# Sheet1.net
KiCad netlist of a schematic drawn in Altium Designer
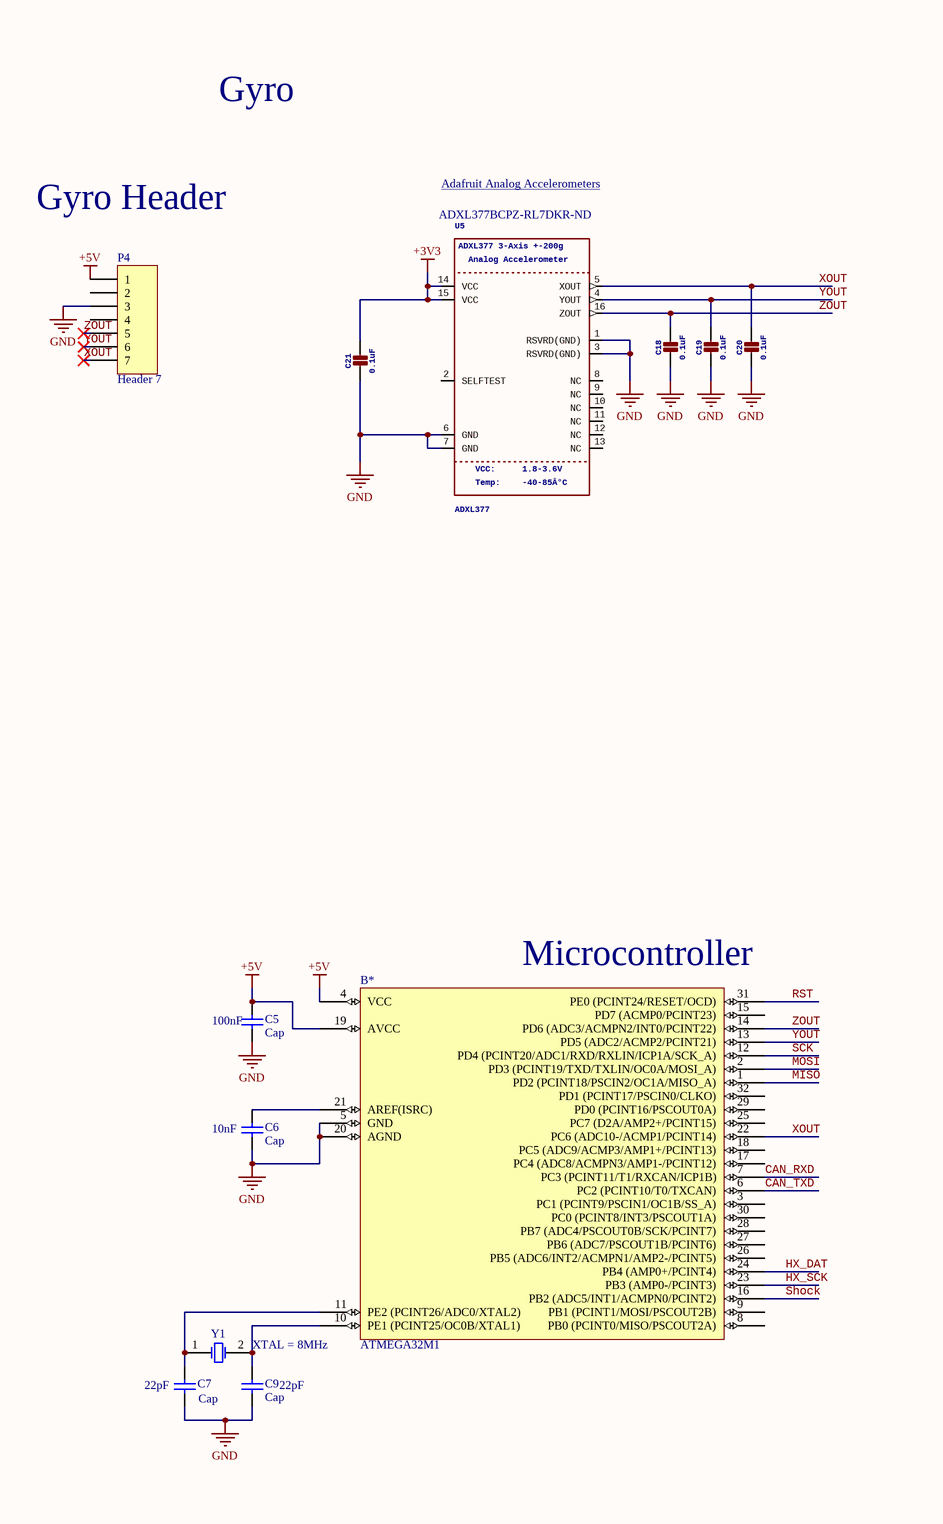
[diagram p0: Sheet1.SchDoc, left]
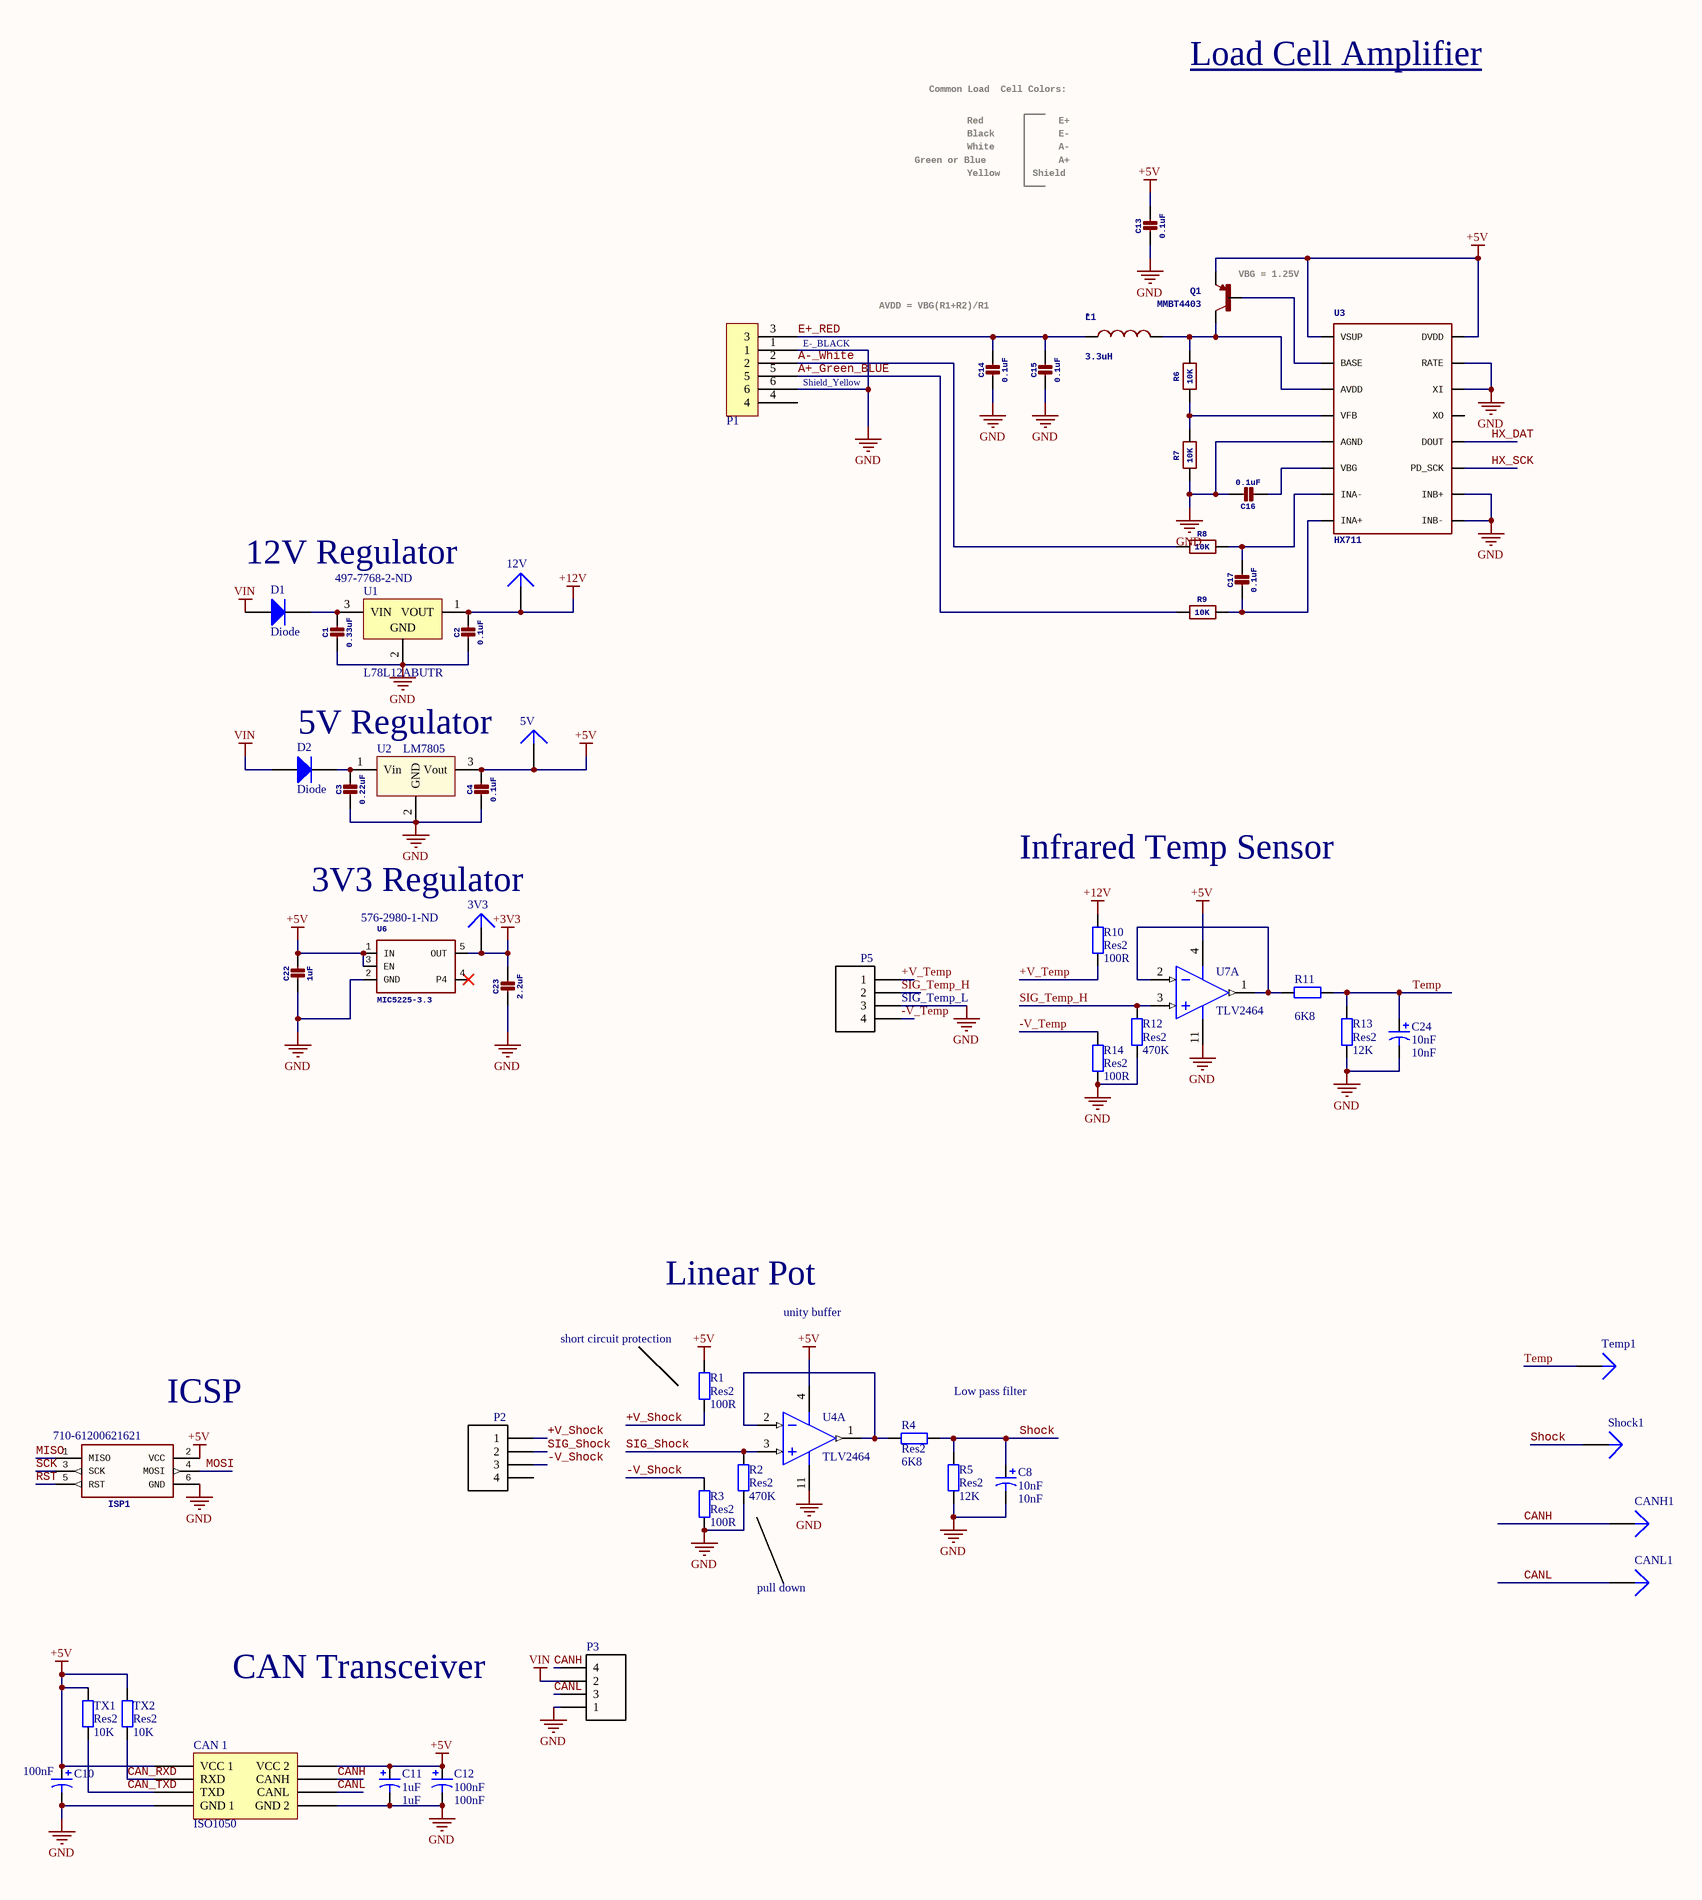
[diagram p1: Sheet1.SchDoc, right]

(export (version "E")
  (design (tool "Eeschema 10.0.6"))
  (components
    (comp (ref "3V3")
      (value "TP")
      (footprint "SMD_TP")
      (description "Test Point")
      (fields (field (name "PUBLISHER") "Altium Limited"))
      (libsource (lib "Miscellaneous Connectors") (part "Plug"))
    )
    (comp (ref "5V")
      (value "TP")
      (footprint "SMD_TP")
      (description "Test Point")
      (fields (field (name "PUBLISHER") "Altium Limited"))
      (libsource (lib "Miscellaneous Connectors") (part "Plug"))
    )
    (comp (ref "12V")
      (value "TP")
      (footprint "SMD_TP")
      (description "Test Point")
      (fields (field (name "PUBLISHER") "Altium Limited"))
      (libsource (lib "Miscellaneous Connectors") (part "Plug"))
    )
    (comp (ref "B*")
      (value "ATMEGA32M1")
      (footprint "QFP80P900X900X120-32N")
      (libsource (lib "Schlib1") (part "ATMEGA32M1"))
    )
    (comp (ref "C1")
      (value "0.33uF")
      (footprint "6-0805_M")
      (libsource (lib "Schlib1") (part "CAP_CERAMIC0805-NOOUTLINE"))
    )
    (comp (ref "C2")
      (value "0.1uF")
      (footprint "6-0805_M")
      (libsource (lib "Schlib1") (part "CAP_CERAMIC0805-NOOUTLINE"))
    )
    (comp (ref "C3")
      (value "0.22uF")
      (footprint "6-0805_M")
      (libsource (lib "Schlib1") (part "CAP_CERAMIC0805-NOOUTLINE"))
    )
    (comp (ref "C4")
      (value "0.1uF")
      (footprint "6-0805_M")
      (libsource (lib "Schlib1") (part "CAP_CERAMIC0805-NOOUTLINE"))
    )
    (comp (ref "C5")
      (value "Cap")
      (footprint "CAP-0805")
      (description "Capacitor")
      (fields (field (name "ALTIUM_VALUE") "100nF") (field (name "PUBLISHER") "Altium Limited"))
      (libsource (lib "Miscellaneous Devices") (part "Cap"))
    )
    (comp (ref "C6")
      (value "Cap")
      (footprint "CAP-0805")
      (description "Capacitor")
      (fields (field (name "ALTIUM_VALUE") "10nF") (field (name "PUBLISHER") "Altium Limited"))
      (libsource (lib "Miscellaneous Devices") (part "Cap"))
    )
    (comp (ref "C7")
      (value "Cap")
      (footprint "CAP-0805")
      (description "Capacitor")
      (fields (field (name "ALTIUM_VALUE") "22pF") (field (name "PUBLISHER") "Altium Limited"))
      (libsource (lib "Miscellaneous Devices") (part "Cap"))
    )
    (comp (ref "C8")
      (value "10nF")
      (footprint "6-0805_M")
      (description "Polarized Capacitor (Surface Mount)")
      (fields (field (name "ALTIUM_VALUE") "10nF") (field (name "PUBLISHER") "Altium Limited"))
      (libsource (lib "Miscellaneous Devices") (part "Cap Pol3"))
    )
    (comp (ref "C9")
      (value "Cap")
      (footprint "CAP-0805")
      (description "Capacitor")
      (fields (field (name "ALTIUM_VALUE") "22pF") (field (name "PUBLISHER") "Altium Limited"))
      (libsource (lib "Miscellaneous Devices") (part "Cap"))
    )
    (comp (ref "C10")
      (value "100nF")
      (footprint "6-0805_M")
      (description "Polarized Capacitor (Surface Mount)")
      (fields (field (name "PUBLISHER") "Altium Limited"))
      (libsource (lib "Miscellaneous Devices") (part "Cap Pol3"))
    )
    (comp (ref "C11")
      (value "1uF")
      (footprint "6-0805_M")
      (description "Polarized Capacitor (Surface Mount)")
      (fields (field (name "ALTIUM_VALUE") "1uF") (field (name "PUBLISHER") "Altium Limited"))
      (libsource (lib "") (part "Cap Pol3_1"))
    )
    (comp (ref "C12")
      (value "100nF")
      (footprint "6-0805_M")
      (description "Polarized Capacitor (Surface Mount)")
      (fields (field (name "ALTIUM_VALUE") "100nF") (field (name "PUBLISHER") "Altium Limited"))
      (libsource (lib "") (part "Cap Pol3_1"))
    )
    (comp (ref "C13")
      (value "0.1uF")
      (footprint "6-0805_M")
      (libsource (lib "Schlib1") (part "CAP_CERAMIC0805-NOOUTLINE"))
    )
    (comp (ref "C14")
      (value "0.1uF")
      (footprint "6-0805_M")
      (libsource (lib "Schlib1") (part "CAP_CERAMIC0805-NOOUTLINE"))
    )
    (comp (ref "C15")
      (value "0.1uF")
      (footprint "6-0805_M")
      (libsource (lib "Schlib1") (part "CAP_CERAMIC0805-NOOUTLINE"))
    )
    (comp (ref "C16")
      (value "0.1uF")
      (footprint "6-0805_M")
      (libsource (lib "") (part "CAP_CERAMIC0805-NOOUTLINE_1"))
    )
    (comp (ref "C17")
      (value "0.1uF")
      (footprint "6-0805_M")
      (libsource (lib "Schlib1") (part "CAP_CERAMIC0805-NOOUTLINE"))
    )
    (comp (ref "C18")
      (value "0.1uF")
      (footprint "0805_10MGAP")
      (libsource (lib "Schlib1") (part "CAP_CERAMIC0805_10MGAP"))
    )
    (comp (ref "C19")
      (value "0.1uF")
      (footprint "0805_10MGAP")
      (libsource (lib "Schlib1") (part "CAP_CERAMIC0805_10MGAP"))
    )
    (comp (ref "C20")
      (value "0.1uF")
      (footprint "0805_10MGAP")
      (libsource (lib "Schlib1") (part "CAP_CERAMIC0805_10MGAP"))
    )
    (comp (ref "C21")
      (value "0.1uF")
      (footprint "0805_10MGAP")
      (libsource (lib "Schlib1") (part "CAP_CERAMIC0805_10MGAP"))
    )
    (comp (ref "C22")
      (value "1uF")
      (footprint "6-0805_M")
      (libsource (lib "Schlib1") (part "CAP_CERAMIC0805-NOOUTLINE"))
    )
    (comp (ref "C23")
      (value "2.2uF")
      (footprint "6-0805_M")
      (libsource (lib "Schlib1") (part "CAP_CERAMIC0805-NOOUTLINE"))
    )
    (comp (ref "C24")
      (value "10nF")
      (footprint "6-0805_M")
      (description "Polarized Capacitor (Surface Mount)")
      (fields (field (name "ALTIUM_VALUE") "10nF") (field (name "PUBLISHER") "Altium Limited"))
      (libsource (lib "Miscellaneous Devices") (part "Cap Pol3"))
    )
    (comp (ref "CAN 1")
      (value "ISO1050")
      (footprint "PcbLib1:ISO1050")
      (description "ISO1050 Isolated Can Transceiver")
      (libsource (lib "Schlib1") (part "ISO1050"))
    )
    (comp (ref "CANH1")
      (value "TP")
      (footprint "SMD_TP")
      (description "Test Point")
      (fields (field (name "PUBLISHER") "Altium Limited"))
      (libsource (lib "Miscellaneous Connectors") (part "Plug"))
    )
    (comp (ref "CANL1")
      (value "TP")
      (footprint "SMD_TP")
      (description "Test Point")
      (fields (field (name "PUBLISHER") "Altium Limited"))
      (libsource (lib "Miscellaneous Connectors") (part "Plug"))
    )
    (comp (ref "D1")
      (value "Diode")
      (footprint "6-0805_M")
      (description "Default Diode")
      (fields (field (name "PUBLISHER") "Altium Limited"))
      (libsource (lib "Miscellaneous Devices") (part "Diode"))
    )
    (comp (ref "D2")
      (value "Diode")
      (footprint "6-0805_M")
      (description "Default Diode")
      (fields (field (name "PUBLISHER") "Altium Limited"))
      (libsource (lib "Miscellaneous Devices") (part "Diode"))
    )
    (comp (ref "ISP1")
      (value "AVRISP-BOX")
      (footprint "HDR2X3")
      (description "AVR ISP HEADERStandard 6 pin header for AVR programming")
      (fields
        (field (name "SUPPLIER PART NUMBER 1") "710-61200621621")
        (field (name "MANUFACTURER") "Wurth Electronics")
        (field (name "MANUFACTURER PART NUMBER") "61200621621")
      )
      (libsource (lib "Schlib1") (part "AVRISP-BOX"))
    )
    (comp (ref "L1")
      (value "3.3uH")
      (footprint "6-0805_M")
      (fields (field (name "NAME") "*"))
      (libsource (lib "SparkFun-Passives") (part "INDUCTOR0805-IND"))
    )
    (comp (ref "P1")
      (value "S06B-PASK-2")
      (footprint "JST_S06B-PASK-2")
      (description "JST (JAPAN SOLDERLESS TERMINALS) - S06B-PASK-2 - HEADER, PA, 6WAY, SIDE, 2MM")
      (libsource (lib "Schlib1") (part "JST-S06B-PASK-2"))
    )
    (comp (ref "P2")
      (value "S04B-PASK-2(LF)(SN)")
      (footprint "JST_S04B-PASK-2(LF)(SN)")
      (description "PA Series 4 Position 2.0mm Through Hole Wire to Board Single Row Shrouded Header")
      (fields (field (name "MP") "S04B-PASK-2_LF__SN_") (field (name "MF") "JST"))
      (libsource (lib "") (part "JST-S04B-PASK-2(LF)(SN)_1"))
    )
    (comp (ref "P3")
      (value "S04B-PASK-2(LF)(SN)")
      (footprint "JST_S04B-PASK-2(LF)(SN)")
      (description "PA Series 4 Position 2.0mm Through Hole Wire to Board Single Row Shrouded Header")
      (fields (field (name "MP") "S04B-PASK-2_LF__SN_") (field (name "MF") "JST"))
      (libsource (lib "Schlib1") (part "JST-S04B-PASK-2(LF)(SN)"))
    )
    (comp (ref "P4")
      (value "Header 7")
      (footprint "HDR1X7")
      (description "Header, 7-Pin")
      (fields (field (name "PUBLISHER") "Altium Limited"))
      (libsource (lib "Miscellaneous Connectors") (part "Header 7"))
    )
    (comp (ref "P5")
      (value "S04B-PASK-2(LF)(SN)")
      (footprint "JST_S04B-PASK-2(LF)(SN)")
      (description "PA Series 4 Position 2.0mm Through Hole Wire to Board Single Row Shrouded Header")
      (fields (field (name "MP") "S04B-PASK-2_LF__SN_") (field (name "MF") "JST"))
      (libsource (lib "") (part "JST-S04B-PASK-2(LF)(SN)_1"))
    )
    (comp (ref "Q1")
      (value "MMBT4403")
      (footprint "SOT23-3")
      (libsource (lib "SparkFun-DiscreteSemi") (part "TRANSISTOR_PNPMMBT4403"))
    )
    (comp (ref "R1")
      (value "Res2")
      (footprint "6-0805_M")
      (description "Resistor")
      (fields (field (name "ALTIUM_VALUE") "100R") (field (name "PUBLISHER") "Altium Limited"))
      (libsource (lib "Miscellaneous Devices") (part "Res2"))
    )
    (comp (ref "R2")
      (value "Res2")
      (footprint "6-0805_M")
      (description "Resistor")
      (fields (field (name "ALTIUM_VALUE") "470K") (field (name "PUBLISHER") "Altium Limited"))
      (libsource (lib "Miscellaneous Devices") (part "Res2"))
    )
    (comp (ref "R3")
      (value "Res2")
      (footprint "6-0805_M")
      (description "Resistor")
      (fields (field (name "ALTIUM_VALUE") "100R") (field (name "PUBLISHER") "Altium Limited"))
      (libsource (lib "Miscellaneous Devices") (part "Res2"))
    )
    (comp (ref "R4")
      (value "Res2")
      (footprint "6-0805_M")
      (description "Resistor")
      (fields (field (name "ALTIUM_VALUE") "6K8") (field (name "PUBLISHER") "Altium Limited"))
      (libsource (lib "") (part "Res2_1"))
    )
    (comp (ref "R5")
      (value "Res2")
      (footprint "6-0805_M")
      (description "Resistor")
      (fields (field (name "ALTIUM_VALUE") "12K") (field (name "PUBLISHER") "Altium Limited"))
      (libsource (lib "Miscellaneous Devices") (part "Res2"))
    )
    (comp (ref "R6")
      (value "10K")
      (footprint "6-0805_M")
      (libsource (lib "Schlib1") (part "RESISTOR0805_NOOUTLINE"))
    )
    (comp (ref "R7")
      (value "10K")
      (footprint "6-0805_M")
      (libsource (lib "Schlib1") (part "RESISTOR0805_NOOUTLINE"))
    )
    (comp (ref "R8")
      (value "10K")
      (footprint "6-0805_M")
      (libsource (lib "Schlib1") (part "RESISTOR0805_NOOUTLINE"))
    )
    (comp (ref "R9")
      (value "10K")
      (footprint "6-0805_M")
      (libsource (lib "Schlib1") (part "RESISTOR0805_NOOUTLINE"))
    )
    (comp (ref "R10")
      (value "Res2")
      (footprint "6-0805_M")
      (description "Resistor")
      (fields (field (name "ALTIUM_VALUE") "100R") (field (name "PUBLISHER") "Altium Limited"))
      (libsource (lib "Miscellaneous Devices") (part "Res2"))
    )
    (comp (ref "R11")
      (value "6K8")
      (footprint "6-0805_M")
      (description "Resistor")
      (fields (field (name "PUBLISHER") "Altium Limited"))
      (libsource (lib "") (part "Res2_1"))
    )
    (comp (ref "R12")
      (value "Res2")
      (footprint "6-0805_M")
      (description "Resistor")
      (fields (field (name "ALTIUM_VALUE") "470K") (field (name "PUBLISHER") "Altium Limited"))
      (libsource (lib "Miscellaneous Devices") (part "Res2"))
    )
    (comp (ref "R13")
      (value "Res2")
      (footprint "6-0805_M")
      (description "Resistor")
      (fields (field (name "ALTIUM_VALUE") "12K") (field (name "PUBLISHER") "Altium Limited"))
      (libsource (lib "Miscellaneous Devices") (part "Res2"))
    )
    (comp (ref "R14")
      (value "Res2")
      (footprint "6-0805_M")
      (description "Resistor")
      (fields (field (name "ALTIUM_VALUE") "100R") (field (name "PUBLISHER") "Altium Limited"))
      (libsource (lib "Miscellaneous Devices") (part "Res2"))
    )
    (comp (ref "Shock1")
      (value "TP")
      (footprint "SMD_TP")
      (description "Test Point")
      (fields (field (name "PUBLISHER") "Altium Limited"))
      (libsource (lib "Miscellaneous Connectors") (part "Plug"))
    )
    (comp (ref "Temp1")
      (value "TP")
      (footprint "SMD_TP")
      (description "Test Point")
      (fields (field (name "PUBLISHER") "Altium Limited"))
      (libsource (lib "Miscellaneous Connectors") (part "Plug"))
    )
    (comp (ref "TX1")
      (value "Res2")
      (footprint "6-0805_M")
      (description "Resistor")
      (fields (field (name "ALTIUM_VALUE") "10K") (field (name "PUBLISHER") "Altium Limited"))
      (libsource (lib "Miscellaneous Devices") (part "Res2"))
    )
    (comp (ref "TX2")
      (value "Res2")
      (footprint "6-0805_M")
      (description "Resistor")
      (fields (field (name "ALTIUM_VALUE") "10K") (field (name "PUBLISHER") "Altium Limited"))
      (libsource (lib "Miscellaneous Devices") (part "Res2"))
    )
    (comp (ref "U1")
      (value "L78L12ABUTR")
      (footprint "SOT-89_M")
      (description "Positive Voltage Regulator, 12V, 4-Pin SOT-89, Tape and Reel")
      (fields
        (field (name "SUPPLIER PART NUMBER 1") "497-7768-2-ND")
        (field (name "MANUFACTURER") "STMicroelectronics")
      )
      (libsource (lib "Schlib1") (part "L78L12ABUTR"))
    )
    (comp (ref "U2")
      (value "LM7805")
      (footprint "SOT-223-2")
      (fields
        (field (name "MANUFACTURER") "Texas Instruments")
        (field (name "MANUFACTURER PART NUMBER") "LM7805MPNOPB")
      )
      (libsource (lib "Schlib1") (part "LM78XX"))
    )
    (comp (ref "U3")
      (value "HX711")
      (footprint "SO16")
      (fields (field (name "LIBRARYNAME") "Testing"))
      (libsource (lib "Schlib1") (part "HX711HX711"))
    )
    (comp (ref "U4")
      (value "TLV2464")
      (footprint "SO14")
      (description "Low Power Quad Operational Amplifier")
      (fields
        (field (name "MANUFACTURER PART NUMBER") "LF347BD")
        (field (name "MANUFACTURER") "Texas Instruments")
      )
      (libsource (lib "Schlib1") (part "LF347"))
    )
    (comp (ref "U5")
      (value "ADXL377")
      (footprint "LFCSP16_LQ")
      (description "ADXL377 +/-200g 3-Axis Analog Accelerometer")
      (fields
        (field (name "ADXL3773-AXIS+-200G") "ADXL377 3-Axis +-200g")
        (field (name "ANALOGACCELEROMETER") "Analog Accelerometer")
        (field (name "VCC") "VCC:")
        (field (name "1.8-3.6V") "1.8-3.6V")
        (field (name "TEMP") "Temp:")
        (field (name "-40-85掳C") "-40-85掳C")
        (field (name "SUPPLIER PART NUMBER 1") "ADXL377BCPZ-RL7DKR-ND")
        (field (name "MANUFACTURER") "Analog Devices")
        (field (name "MANUFACTURER PART NUMBER") "ADXL377BCPZ-RL7")
      )
      (libsource (lib "Schlib1") (part "ACCEL_ADXL377"))
    )
    (comp (ref "U6")
      (value "MIC5225-3.3")
      (footprint "SOT95P280X145-5N")
      (fields
        (field (name "SUPPLIER PART NUMBER 1") "576-2980-1-ND")
        (field (name "MANUFACTURER") "Microchip Micrel")
        (field (name "MANUFACTURER PART NUMBER") "MIC5225-3.3YM5TR")
      )
      (libsource (lib "Schlib1") (part "VREG_SOT23-5"))
    )
    (comp (ref "U7")
      (value "TLV2464")
      (footprint "SO14")
      (description "Low Power Quad Operational Amplifier")
      (fields
        (field (name "MANUFACTURER PART NUMBER") "LF347BD")
        (field (name "MANUFACTURER") "Texas Instruments")
      )
      (libsource (lib "vh_altium_library") (part "LF347"))
    )
    (comp (ref "Y1")
      (value "XTAL = 8MHz")
      (footprint "R38")
      (description "Crystal Oscillator")
      (fields (field (name "PUBLISHER") "Altium Limited"))
      (libsource (lib "Miscellaneous Devices") (part "XTAL"))
    )
  )
  (nets
    (net (code "1") (name "+3V3") (class "Default")
      (node (ref "3V3") (pin "1") (pinfunction "1_1") (pintype "passive"))
      (node (ref "C21") (pin "1") (pinfunction "1_1") (pintype "passive"))
      (node (ref "C23") (pin "1") (pinfunction "1_1") (pintype "passive"))
      (node (ref "U5") (pin "14") (pinfunction "VCC_14") (pintype "power_in"))
      (node (ref "U5") (pin "15") (pinfunction "VCC_15") (pintype "power_in"))
      (node (ref "U6") (pin "5") (pinfunction "OUT_5") (pintype "power_in"))
    )
    (net (code "2") (name "+5V") (class "Default")
      (node (ref "5V") (pin "1") (pinfunction "1_1") (pintype "passive"))
      (node (ref "B*") (pin "19") (pinfunction "AVCC_19") (pintype "bidirectional"))
      (node (ref "B*") (pin "4") (pinfunction "VCC_4") (pintype "bidirectional"))
      (node (ref "C10") (pin "1") (pinfunction "1_1") (pintype "passive"))
      (node (ref "C11") (pin "1") (pinfunction "1_1") (pintype "passive"))
      (node (ref "C12") (pin "1") (pinfunction "1_1") (pintype "passive"))
      (node (ref "C13") (pin "1") (pinfunction "1_1") (pintype "passive"))
      (node (ref "C22") (pin "1") (pinfunction "1_1") (pintype "passive"))
      (node (ref "C4") (pin "1") (pinfunction "1_1") (pintype "passive"))
      (node (ref "C5") (pin "2") (pinfunction "2_2") (pintype "passive"))
      (node (ref "CAN 1") (pin "1") (pinfunction "VCC_1_1") (pintype "passive"))
      (node (ref "CAN 1") (pin "8") (pinfunction "VCC_2_8") (pintype "passive"))
      (node (ref "ISP1") (pin "2") (pinfunction "VCC_2") (pintype "power_in"))
      (node (ref "P4") (pin "1") (pinfunction "1_1") (pintype "passive"))
      (node (ref "Q1") (pin "2") (pinfunction "E_2") (pintype "passive"))
      (node (ref "R1") (pin "2") (pinfunction "2_2") (pintype "passive"))
      (node (ref "TX1") (pin "2") (pinfunction "2_2") (pintype "passive"))
      (node (ref "TX2") (pin "2") (pinfunction "2_2") (pintype "passive"))
      (node (ref "U2") (pin "3") (pinfunction "Vout_3") (pintype "passive"))
      (node (ref "U3") (pin "1") (pinfunction "VSUP_1") (pintype "passive"))
      (node (ref "U3") (pin "16") (pinfunction "DVDD_16") (pintype "passive"))
      (node (ref "U4") (pin "4") (pinfunction "VCC_4") (pintype "power_in"))
      (node (ref "U6") (pin "1") (pinfunction "IN_1") (pintype "power_in"))
      (node (ref "U6") (pin "3") (pinfunction "EN_3") (pintype "passive"))
      (node (ref "U7") (pin "4") (pinfunction "VCC_4") (pintype "power_in"))
    )
    (net (code "3") (name "+12V") (class "Default")
      (node (ref "12V") (pin "1") (pinfunction "1_1") (pintype "passive"))
      (node (ref "C2") (pin "1") (pinfunction "1_1") (pintype "passive"))
      (node (ref "R10") (pin "2") (pinfunction "2_2") (pintype "passive"))
      (node (ref "U1") (pin "1") (pinfunction "VOUT_1") (pintype "power_in"))
    )
    (net (code "4") (name "/+V_Shock") (class "Default")
      (node (ref "P2") (pin "1") (pinfunction "1_1") (pintype "passive"))
      (node (ref "R1") (pin "1") (pinfunction "1_1") (pintype "passive"))
    )
    (net (code "5") (name "/+V_Temp") (class "Default")
      (node (ref "P5") (pin "1") (pinfunction "1_1") (pintype "passive"))
      (node (ref "R10") (pin "1") (pinfunction "1_1") (pintype "passive"))
    )
    (net (code "6") (name "/-V_Shock") (class "Default")
      (node (ref "P2") (pin "3") (pinfunction "3_3") (pintype "passive"))
      (node (ref "R3") (pin "2") (pinfunction "2_2") (pintype "passive"))
    )
    (net (code "7") (name "/-V_Temp") (class "Default")
      (node (ref "P5") (pin "4") (pinfunction "4_4") (pintype "passive"))
      (node (ref "R14") (pin "2") (pinfunction "2_2") (pintype "passive"))
    )
    (net (code "8") (name "/A+_Green_BLUE") (class "Default")
      (node (ref "P1") (pin "5") (pinfunction "5_5") (pintype "passive"))
      (node (ref "R9") (pin "1") (pinfunction "1_1") (pintype "passive"))
    )
    (net (code "9") (name "/A-_White") (class "Default")
      (node (ref "P1") (pin "2") (pinfunction "2_2") (pintype "passive"))
      (node (ref "R8") (pin "1") (pinfunction "1_1") (pintype "passive"))
    )
    (net (code "10") (name "/CANH") (class "Default")
      (node (ref "CAN 1") (pin "7") (pinfunction "CANH_7") (pintype "passive"))
      (node (ref "CANH1") (pin "1") (pinfunction "1_1") (pintype "passive"))
      (node (ref "P3") (pin "4") (pinfunction "4_4") (pintype "passive"))
    )
    (net (code "11") (name "/CANL") (class "Default")
      (node (ref "CAN 1") (pin "6") (pinfunction "CANL_6") (pintype "passive"))
      (node (ref "CANL1") (pin "1") (pinfunction "1_1") (pintype "passive"))
      (node (ref "P3") (pin "3") (pinfunction "3_3") (pintype "passive"))
    )
    (net (code "12") (name "/CAN_RXD") (class "Default")
      (node (ref "B*") (pin "7") (pinfunction "PC3_(PCINT11/T1/RXCAN/ICP1B)_7") (pintype "bidirectional"))
      (node (ref "CAN 1") (pin "2") (pinfunction "RXD_2") (pintype "passive"))
      (node (ref "TX2") (pin "1") (pinfunction "1_1") (pintype "passive"))
    )
    (net (code "13") (name "/CAN_TXD") (class "Default")
      (node (ref "B*") (pin "6") (pinfunction "PC2_(PCINT10/T0/TXCAN)_6") (pintype "bidirectional"))
      (node (ref "CAN 1") (pin "3") (pinfunction "TXD_3") (pintype "passive"))
      (node (ref "TX1") (pin "1") (pinfunction "1_1") (pintype "passive"))
    )
    (net (code "14") (name "/E+_RED") (class "Default")
      (node (ref "C14") (pin "1") (pinfunction "1_1") (pintype "passive"))
      (node (ref "C15") (pin "1") (pinfunction "1_1") (pintype "passive"))
      (node (ref "L1") (pin "1") (pinfunction "1_1") (pintype "passive"))
      (node (ref "P1") (pin "3") (pinfunction "3_3") (pintype "passive"))
    )
    (net (code "15") (name "/HX_DAT") (class "Default")
      (node (ref "B*") (pin "24") (pinfunction "PB4_(AMP0+/PCINT4)_24") (pintype "bidirectional"))
      (node (ref "U3") (pin "12") (pinfunction "DOUT_12") (pintype "passive"))
    )
    (net (code "16") (name "/HX_SCK") (class "Default")
      (node (ref "B*") (pin "23") (pinfunction "PB3_(AMP0-/PCINT3)_23") (pintype "bidirectional"))
      (node (ref "U3") (pin "11") (pinfunction "PD_SCK_11") (pintype "passive"))
    )
    (net (code "17") (name "/MISO") (class "Default")
      (node (ref "B*") (pin "1") (pinfunction "PD2_(PCINT18/PSCIN2/OC1A/MISO_A)_1") (pintype "bidirectional"))
      (node (ref "ISP1") (pin "1") (pinfunction "MISO_1") (pintype "passive"))
    )
    (net (code "18") (name "/MOSI") (class "Default")
      (node (ref "B*") (pin "2") (pinfunction "PD3_(PCINT19/TXD/TXLIN/OC0A/MOSI_A)_2") (pintype "bidirectional"))
      (node (ref "ISP1") (pin "4") (pinfunction "MOSI_4") (pintype "output"))
    )
    (net (code "19") (name "/RST") (class "Default")
      (node (ref "B*") (pin "31") (pinfunction "PE0_(PCINT24/RESET/OCD)_31") (pintype "bidirectional"))
      (node (ref "ISP1") (pin "5") (pinfunction "RST_5") (pintype "output"))
    )
    (net (code "20") (name "/SCK") (class "Default")
      (node (ref "B*") (pin "12") (pinfunction "PD4_(PCINT20/ADC1/RXD/RXLIN/ICP1A/SCK_A)_12") (pintype "bidirectional"))
      (node (ref "ISP1") (pin "3") (pinfunction "SCK_3") (pintype "output"))
    )
    (net (code "21") (name "/SIG_Shock") (class "Default")
      (node (ref "P2") (pin "2") (pinfunction "2_2") (pintype "passive"))
      (node (ref "R2") (pin "2") (pinfunction "2_2") (pintype "passive"))
      (node (ref "U4") (pin "3") (pinfunction "1_IN+_3") (pintype "input"))
    )
    (net (code "22") (name "/SIG_Temp_H") (class "Default")
      (node (ref "P5") (pin "2") (pinfunction "2_2") (pintype "passive"))
      (node (ref "R12") (pin "2") (pinfunction "2_2") (pintype "passive"))
      (node (ref "U7") (pin "3") (pinfunction "1_IN+_3") (pintype "input"))
    )
    (net (code "23") (name "/Shock") (class "Default")
      (node (ref "B*") (pin "16") (pinfunction "PB2_(ADC5/INT1/ACMPN0/PCINT2)_16") (pintype "bidirectional"))
      (node (ref "C8") (pin "1") (pinfunction "1_1") (pintype "passive"))
      (node (ref "R4") (pin "1") (pinfunction "1_1") (pintype "passive"))
      (node (ref "R5") (pin "2") (pinfunction "2_2") (pintype "passive"))
      (node (ref "Shock1") (pin "1") (pinfunction "1_1") (pintype "passive"))
    )
    (net (code "24") (name "/Temp") (class "Default")
      (node (ref "C24") (pin "1") (pinfunction "1_1") (pintype "passive"))
      (node (ref "R11") (pin "1") (pinfunction "1_1") (pintype "passive"))
      (node (ref "R13") (pin "2") (pinfunction "2_2") (pintype "passive"))
      (node (ref "Temp1") (pin "1") (pinfunction "1_1") (pintype "passive"))
    )
    (net (code "25") (name "/XOUT") (class "Default")
      (node (ref "B*") (pin "22") (pinfunction "PC6_(ADC10-/ACMP1/PCINT14)_22") (pintype "bidirectional"))
      (node (ref "C20") (pin "1") (pinfunction "1_1") (pintype "passive"))
      (node (ref "P4") (pin "7") (pinfunction "7_7") (pintype "passive"))
      (node (ref "U5") (pin "5") (pinfunction "XOUT_5") (pintype "output"))
    )
    (net (code "26") (name "/YOUT") (class "Default")
      (node (ref "B*") (pin "13") (pinfunction "PD5_(ADC2/ACMP2/PCINT21)_13") (pintype "bidirectional"))
      (node (ref "C19") (pin "1") (pinfunction "1_1") (pintype "passive"))
      (node (ref "P4") (pin "6") (pinfunction "6_6") (pintype "passive"))
      (node (ref "U5") (pin "4") (pinfunction "YOUT_4") (pintype "output"))
    )
    (net (code "27") (name "/ZOUT") (class "Default")
      (node (ref "B*") (pin "14") (pinfunction "PD6_(ADC3/ACMPN2/INT0/PCINT22)_14") (pintype "bidirectional"))
      (node (ref "C18") (pin "1") (pinfunction "1_1") (pintype "passive"))
      (node (ref "P4") (pin "5") (pinfunction "5_5") (pintype "passive"))
      (node (ref "U5") (pin "16") (pinfunction "ZOUT_16") (pintype "output"))
    )
    (net (code "28") (name "GND") (class "Default")
      (node (ref "B*") (pin "20") (pinfunction "AGND_20") (pintype "bidirectional"))
      (node (ref "B*") (pin "5") (pinfunction "GND_5") (pintype "bidirectional"))
      (node (ref "C1") (pin "2") (pinfunction "2_2") (pintype "passive"))
      (node (ref "C10") (pin "2") (pinfunction "2_2") (pintype "passive"))
      (node (ref "C11") (pin "2") (pinfunction "2_2") (pintype "passive"))
      (node (ref "C12") (pin "2") (pinfunction "2_2") (pintype "passive"))
      (node (ref "C13") (pin "2") (pinfunction "2_2") (pintype "passive"))
      (node (ref "C14") (pin "2") (pinfunction "2_2") (pintype "passive"))
      (node (ref "C15") (pin "2") (pinfunction "2_2") (pintype "passive"))
      (node (ref "C16") (pin "1") (pinfunction "1_1") (pintype "passive"))
      (node (ref "C18") (pin "2") (pinfunction "2_2") (pintype "passive"))
      (node (ref "C19") (pin "2") (pinfunction "2_2") (pintype "passive"))
      (node (ref "C2") (pin "2") (pinfunction "2_2") (pintype "passive"))
      (node (ref "C20") (pin "2") (pinfunction "2_2") (pintype "passive"))
      (node (ref "C21") (pin "2") (pinfunction "2_2") (pintype "passive"))
      (node (ref "C22") (pin "2") (pinfunction "2_2") (pintype "passive"))
      (node (ref "C23") (pin "2") (pinfunction "2_2") (pintype "passive"))
      (node (ref "C24") (pin "2") (pinfunction "2_2") (pintype "passive"))
      (node (ref "C3") (pin "2") (pinfunction "2_2") (pintype "passive"))
      (node (ref "C4") (pin "2") (pinfunction "2_2") (pintype "passive"))
      (node (ref "C5") (pin "1") (pinfunction "1_1") (pintype "passive"))
      (node (ref "C6") (pin "1") (pinfunction "1_1") (pintype "passive"))
      (node (ref "C7") (pin "1") (pinfunction "1_1") (pintype "passive"))
      (node (ref "C8") (pin "2") (pinfunction "2_2") (pintype "passive"))
      (node (ref "C9") (pin "1") (pinfunction "1_1") (pintype "passive"))
      (node (ref "CAN 1") (pin "4") (pinfunction "GND_1_4") (pintype "passive"))
      (node (ref "CAN 1") (pin "5") (pinfunction "GND_2_5") (pintype "passive"))
      (node (ref "ISP1") (pin "6") (pinfunction "GND_6") (pintype "power_in"))
      (node (ref "P1") (pin "1") (pinfunction "1_1") (pintype "passive"))
      (node (ref "P1") (pin "6") (pinfunction "6_6") (pintype "passive"))
      (node (ref "P3") (pin "1") (pinfunction "1_1") (pintype "passive"))
      (node (ref "P4") (pin "3") (pinfunction "3_3") (pintype "passive"))
      (node (ref "P5") (pin "3") (pinfunction "3_3") (pintype "passive"))
      (node (ref "R12") (pin "1") (pinfunction "1_1") (pintype "passive"))
      (node (ref "R13") (pin "1") (pinfunction "1_1") (pintype "passive"))
      (node (ref "R14") (pin "1") (pinfunction "1_1") (pintype "passive"))
      (node (ref "R2") (pin "1") (pinfunction "1_1") (pintype "passive"))
      (node (ref "R3") (pin "1") (pinfunction "1_1") (pintype "passive"))
      (node (ref "R5") (pin "1") (pinfunction "1_1") (pintype "passive"))
      (node (ref "R7") (pin "1") (pinfunction "1_1") (pintype "passive"))
      (node (ref "U1") (pin "2") (pinfunction "GND_2") (pintype "power_in"))
      (node (ref "U2") (pin "2") (pinfunction "GND_2") (pintype "passive"))
      (node (ref "U3") (pin "10") (pinfunction "INB+_10") (pintype "passive"))
      (node (ref "U3") (pin "14") (pinfunction "XI_14") (pintype "passive"))
      (node (ref "U3") (pin "15") (pinfunction "RATE_15") (pintype "passive"))
      (node (ref "U3") (pin "5") (pinfunction "AGND_5") (pintype "passive"))
      (node (ref "U3") (pin "9") (pinfunction "INB-_9") (pintype "passive"))
      (node (ref "U4") (pin "11") (pinfunction "VEE_11") (pintype "power_in"))
      (node (ref "U5") (pin "1") (pinfunction "RSVRD(GND)_1") (pintype "passive"))
      (node (ref "U5") (pin "3") (pinfunction "RSVRD(GND)_3") (pintype "passive"))
      (node (ref "U5") (pin "6") (pinfunction "GND_6") (pintype "power_in"))
      (node (ref "U5") (pin "7") (pinfunction "GND_7") (pintype "power_in"))
      (node (ref "U6") (pin "2") (pinfunction "GND_2") (pintype "power_in"))
      (node (ref "U7") (pin "11") (pinfunction "VEE_11") (pintype "power_in"))
    )
    (net (code "29") (name "Net-(B*-AREF(ISRC))") (class "Default")
      (node (ref "B*") (pin "21") (pinfunction "AREF(ISRC)_21") (pintype "bidirectional"))
      (node (ref "C6") (pin "2") (pinfunction "2_2") (pintype "passive"))
    )
    (net (code "30") (name "Net-(B*-PE1_(PCINT25{slash}OC0B{slash}XTAL1))") (class "Default")
      (node (ref "B*") (pin "10") (pinfunction "PE1_(PCINT25/OC0B/XTAL1)_10") (pintype "bidirectional"))
      (node (ref "C9") (pin "2") (pinfunction "2_2") (pintype "passive"))
      (node (ref "Y1") (pin "2") (pinfunction "OSC2_2") (pintype "passive"))
    )
    (net (code "31") (name "Net-(B*-PE2_(PCINT26{slash}ADC0{slash}XTAL2))") (class "Default")
      (node (ref "B*") (pin "11") (pinfunction "PE2_(PCINT26/ADC0/XTAL2)_11") (pintype "bidirectional"))
      (node (ref "C7") (pin "2") (pinfunction "2_2") (pintype "passive"))
      (node (ref "Y1") (pin "1") (pinfunction "OSC1_1") (pintype "passive"))
    )
    (net (code "32") (name "Net-(D1-K)") (class "Default")
      (node (ref "C1") (pin "1") (pinfunction "1_1") (pintype "passive"))
      (node (ref "D1") (pin "2") (pinfunction "K_2") (pintype "passive"))
      (node (ref "U1") (pin "3") (pinfunction "VIN_3") (pintype "power_in"))
    )
    (net (code "33") (name "Net-(D2-K)") (class "Default")
      (node (ref "C3") (pin "1") (pinfunction "1_1") (pintype "passive"))
      (node (ref "D2") (pin "2") (pinfunction "K_2") (pintype "passive"))
      (node (ref "U2") (pin "1") (pinfunction "Vin_1") (pintype "passive"))
    )
    (net (code "34") (name "Net-(Q1-B)") (class "Default")
      (node (ref "Q1") (pin "1") (pinfunction "B_1") (pintype "passive"))
      (node (ref "U3") (pin "2") (pinfunction "BASE_2") (pintype "passive"))
    )
    (net (code "35") (name "Net-(Q1-C)") (class "Default")
      (node (ref "L1") (pin "2") (pinfunction "2_2") (pintype "passive"))
      (node (ref "Q1") (pin "3") (pinfunction "C_3") (pintype "passive"))
      (node (ref "R6") (pin "2") (pinfunction "2_2") (pintype "passive"))
      (node (ref "U3") (pin "3") (pinfunction "AVDD_3") (pintype "passive"))
    )
    (net (code "36") (name "Net-(U3-INA+)") (class "Default")
      (node (ref "C17") (pin "2") (pinfunction "2_2") (pintype "passive"))
      (node (ref "R9") (pin "2") (pinfunction "2_2") (pintype "passive"))
      (node (ref "U3") (pin "8") (pinfunction "INA+_8") (pintype "passive"))
    )
    (net (code "37") (name "Net-(U3-INA-)") (class "Default")
      (node (ref "C17") (pin "1") (pinfunction "1_1") (pintype "passive"))
      (node (ref "R8") (pin "2") (pinfunction "2_2") (pintype "passive"))
      (node (ref "U3") (pin "7") (pinfunction "INA-_7") (pintype "passive"))
    )
    (net (code "38") (name "Net-(U3-VBG)") (class "Default")
      (node (ref "C16") (pin "2") (pinfunction "2_2") (pintype "passive"))
      (node (ref "U3") (pin "6") (pinfunction "VBG_6") (pintype "passive"))
    )
    (net (code "39") (name "Net-(U3-VFB)") (class "Default")
      (node (ref "R6") (pin "1") (pinfunction "1_1") (pintype "passive"))
      (node (ref "R7") (pin "2") (pinfunction "2_2") (pintype "passive"))
      (node (ref "U3") (pin "4") (pinfunction "VFB_4") (pintype "passive"))
    )
    (net (code "40") (name "Net-(U4A-1_IN-)") (class "Default")
      (node (ref "R4") (pin "2") (pinfunction "2_2") (pintype "passive"))
      (node (ref "U4") (pin "1") (pinfunction "1_OUT_1") (pintype "output"))
      (node (ref "U4") (pin "2") (pinfunction "1_IN-_2") (pintype "input"))
    )
    (net (code "41") (name "Net-(U7A-1_IN-)") (class "Default")
      (node (ref "R11") (pin "2") (pinfunction "2_2") (pintype "passive"))
      (node (ref "U7") (pin "1") (pinfunction "1_OUT_1") (pintype "output"))
      (node (ref "U7") (pin "2") (pinfunction "1_IN-_2") (pintype "input"))
    )
    (net (code "42") (name "VIN") (class "Default")
      (node (ref "D1") (pin "1") (pinfunction "A_1") (pintype "passive"))
      (node (ref "D2") (pin "1") (pinfunction "A_1") (pintype "passive"))
      (node (ref "P3") (pin "2") (pinfunction "2_2") (pintype "passive"))
    )
    (net (code "43") (name "unconnected-(B*-PB0_(PCINT0{slash}MISO{slash}PSCOUT2A)-Pad8)") (class "Default")
      (node (ref "B*") (pin "8") (pinfunction "PB0_(PCINT0/MISO/PSCOUT2A)_8") (pintype "bidirectional"))
    )
    (net (code "44") (name "unconnected-(B*-PB1_(PCINT1{slash}MOSI{slash}PSCOUT2B)-Pad9)") (class "Default")
      (node (ref "B*") (pin "9") (pinfunction "PB1_(PCINT1/MOSI/PSCOUT2B)_9") (pintype "bidirectional"))
    )
    (net (code "45") (name "unconnected-(B*-PB5_(ADC6{slash}INT2{slash}ACMPN1{slash}AMP2-{slash}PCINT5)-Pad26)") (class "Default")
      (node (ref "B*") (pin "26") (pinfunction "PB5_(ADC6/INT2/ACMPN1/AMP2-/PCINT5)_26") (pintype "bidirectional"))
    )
    (net (code "46") (name "unconnected-(B*-PB6_(ADC7{slash}PSCOUT1B{slash}PCINT6)-Pad27)") (class "Default")
      (node (ref "B*") (pin "27") (pinfunction "PB6_(ADC7/PSCOUT1B/PCINT6)_27") (pintype "bidirectional"))
    )
    (net (code "47") (name "unconnected-(B*-PB7_(ADC4{slash}PSCOUT0B{slash}SCK{slash}PCINT7)-Pad28)") (class "Default")
      (node (ref "B*") (pin "28") (pinfunction "PB7_(ADC4/PSCOUT0B/SCK/PCINT7)_28") (pintype "bidirectional"))
    )
    (net (code "48") (name "unconnected-(B*-PC0_(PCINT8{slash}INT3{slash}PSCOUT1A)-Pad30)") (class "Default")
      (node (ref "B*") (pin "30") (pinfunction "PC0_(PCINT8/INT3/PSCOUT1A)_30") (pintype "bidirectional"))
    )
    (net (code "49") (name "unconnected-(B*-PC1_(PCINT9{slash}PSCIN1{slash}OC1B{slash}SS_A)-Pad3)") (class "Default")
      (node (ref "B*") (pin "3") (pinfunction "PC1_(PCINT9/PSCIN1/OC1B/SS_A)_3") (pintype "bidirectional"))
    )
    (net (code "50") (name "unconnected-(B*-PC4_(ADC8{slash}ACMPN3{slash}AMP1-{slash}PCINT12)-Pad17)") (class "Default")
      (node (ref "B*") (pin "17") (pinfunction "PC4_(ADC8/ACMPN3/AMP1-/PCINT12)_17") (pintype "bidirectional"))
    )
    (net (code "51") (name "unconnected-(B*-PC5_(ADC9{slash}ACMP3{slash}AMP1+{slash}PCINT13)-Pad18)") (class "Default")
      (node (ref "B*") (pin "18") (pinfunction "PC5_(ADC9/ACMP3/AMP1+/PCINT13)_18") (pintype "bidirectional"))
    )
    (net (code "52") (name "unconnected-(B*-PC7_(D2A{slash}AMP2+{slash}PCINT15)-Pad25)") (class "Default")
      (node (ref "B*") (pin "25") (pinfunction "PC7_(D2A/AMP2+/PCINT15)_25") (pintype "bidirectional"))
    )
    (net (code "53") (name "unconnected-(B*-PD0_(PCINT16{slash}PSCOUT0A)-Pad29)") (class "Default")
      (node (ref "B*") (pin "29") (pinfunction "PD0_(PCINT16/PSCOUT0A)_29") (pintype "bidirectional"))
    )
    (net (code "54") (name "unconnected-(B*-PD1_(PCINT17{slash}PSCIN0{slash}CLKO)-Pad32)") (class "Default")
      (node (ref "B*") (pin "32") (pinfunction "PD1_(PCINT17/PSCIN0/CLKO)_32") (pintype "bidirectional"))
    )
    (net (code "55") (name "unconnected-(B*-PD7_(ACMP0{slash}PCINT23)-Pad15)") (class "Default")
      (node (ref "B*") (pin "15") (pinfunction "PD7_(ACMP0/PCINT23)_15") (pintype "bidirectional"))
    )
    (net (code "56") (name "unconnected-(P1-Pad4)") (class "Default")
      (node (ref "P1") (pin "4") (pinfunction "4_4") (pintype "passive"))
    )
    (net (code "57") (name "unconnected-(P2-Pad4)") (class "Default")
      (node (ref "P2") (pin "4") (pinfunction "4_4") (pintype "passive"))
    )
    (net (code "58") (name "unconnected-(P4-Pad2)") (class "Default")
      (node (ref "P4") (pin "2") (pinfunction "2_2") (pintype "passive"))
    )
    (net (code "59") (name "unconnected-(P4-Pad4)") (class "Default")
      (node (ref "P4") (pin "4") (pinfunction "4_4") (pintype "passive"))
    )
    (net (code "60") (name "unconnected-(U3-XO-Pad13)") (class "Default")
      (node (ref "U3") (pin "13") (pinfunction "XO_13") (pintype "passive"))
    )
    (net (code "61") (name "unconnected-(U5-NC-Pad8)") (class "Default")
      (node (ref "U5") (pin "8") (pinfunction "NC_8") (pintype "passive"))
    )
    (net (code "62") (name "unconnected-(U5-NC-Pad9)") (class "Default")
      (node (ref "U5") (pin "9") (pinfunction "NC_9") (pintype "passive"))
    )
    (net (code "63") (name "unconnected-(U5-NC-Pad10)") (class "Default")
      (node (ref "U5") (pin "10") (pinfunction "NC_10") (pintype "passive"))
    )
    (net (code "64") (name "unconnected-(U5-NC-Pad11)") (class "Default")
      (node (ref "U5") (pin "11") (pinfunction "NC_11") (pintype "passive"))
    )
    (net (code "65") (name "unconnected-(U5-NC-Pad12)") (class "Default")
      (node (ref "U5") (pin "12") (pinfunction "NC_12") (pintype "passive"))
    )
    (net (code "66") (name "unconnected-(U5-NC-Pad13)") (class "Default")
      (node (ref "U5") (pin "13") (pinfunction "NC_13") (pintype "passive"))
    )
    (net (code "67") (name "unconnected-(U5-SELFTEST-Pad2)") (class "Default")
      (node (ref "U5") (pin "2") (pinfunction "SELFTEST_2") (pintype "passive"))
    )
    (net (code "68") (name "unconnected-(U6-P4-Pad4)") (class "Default")
      (node (ref "U6") (pin "4") (pinfunction "P4_4") (pintype "passive+no_connect"))
    )
  )
)
